# uStar.net
KiCad netlist of a schematic drawn in EAGLE
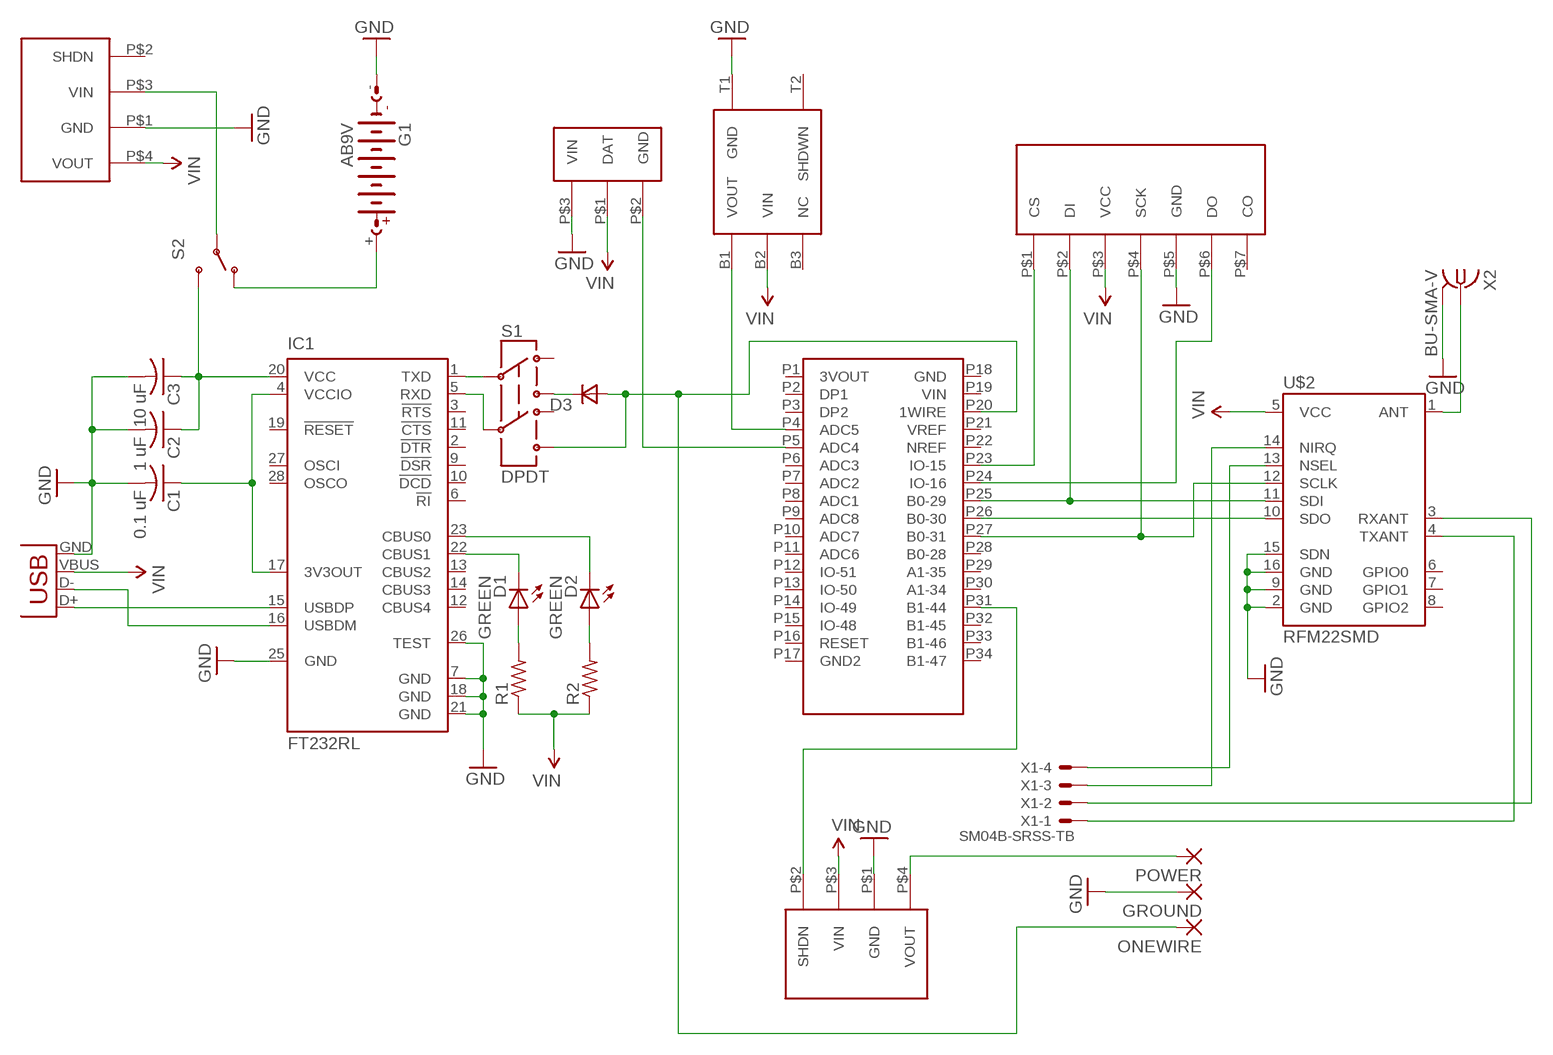
[diagram p0: schematic, sheet 1]

(export (version "E")
  (design (tool "Eeschema 10.0.6"))
  (components
    (comp (ref "C1")
      (value "0.1 uF")
      (footprint "eagle-import:C0805")
      (libsource (lib "eagle-import") (part "C-USC0805"))
    )
    (comp (ref "C2")
      (value "1 uF")
      (footprint "eagle-import:C0805")
      (libsource (lib "eagle-import") (part "C-USC0805"))
    )
    (comp (ref "C3")
      (value "10 uF")
      (footprint "eagle-import:C0805")
      (libsource (lib "eagle-import") (part "C-USC0805"))
    )
    (comp (ref "D1")
      (value "GREEN")
      (footprint "eagle-import:LED-0603")
      (libsource (lib "eagle-import") (part "LED-GREEN0603"))
    )
    (comp (ref "D2")
      (value "GREEN")
      (footprint "eagle-import:LED-0603")
      (libsource (lib "eagle-import") (part "LED-GREEN0603"))
    )
    (comp (ref "D3")
      (value "DSOD323")
      (footprint "eagle-import:SOD323")
      (fields (field (name "MPN") "CDSOD323-T05C"))
      (libsource (lib "eagle-import") (part "DSOD323"))
    )
    (comp (ref "G1")
      (value "AB9V")
      (footprint "eagle-import:AB9V")
      (libsource (lib "eagle-import") (part "AB9V"))
    )
    (comp (ref "GROUND")
      (value "1,6/0,9")
      (footprint "eagle-import:1,6_0,9")
      (libsource (lib "eagle-import") (part "1,6/0,9"))
    )
    (comp (ref "IC1")
      (value "FT232RL")
      (footprint "eagle-import:SSOP28")
      (libsource (lib "eagle-import") (part "FT232RL"))
    )
    (comp (ref "JP1")
      (value "USBSMD")
      (footprint "eagle-import:USB-MINIB")
      (libsource (lib "eagle-import") (part "USBSMD"))
    )
    (comp (ref "ONEWIRE")
      (value "1,6/0,9")
      (footprint "eagle-import:1,6_0,9")
      (libsource (lib "eagle-import") (part "1,6/0,9"))
    )
    (comp (ref "POWER")
      (value "1,6/0,9")
      (footprint "eagle-import:1,6_0,9")
      (libsource (lib "eagle-import") (part "1,6/0,9"))
    )
    (comp (ref "R1")
      (value "R-US_R0603")
      (footprint "eagle-import:R0603")
      (libsource (lib "eagle-import") (part "R-US_R0603"))
    )
    (comp (ref "R2")
      (value "R-US_R0603")
      (footprint "eagle-import:R0603")
      (libsource (lib "eagle-import") (part "R-US_R0603"))
    )
    (comp (ref "S1")
      (value "DPDT")
      (footprint "eagle-import:AYZ0202")
      (libsource (lib "eagle-import") (part "SWITCH-DPDTAYZ0202"))
    )
    (comp (ref "S2")
      (value "SWITCH-SPDTSMD2")
      (footprint "eagle-import:SWITCH-SPDT-SMD")
      (libsource (lib "eagle-import") (part "SWITCH-SPDTSMD2"))
    )
    (comp (ref "U$1")
      (value "APP_CORE")
      (footprint "eagle-import:APPCORE_RECEIVER")
      (libsource (lib "eagle-import") (part "APP_CORE"))
    )
    (comp (ref "U$2")
      (value "RFM22SMD")
      (footprint "eagle-import:RFM22-XXX-S2")
      (libsource (lib "eagle-import") (part "RFM22SMD"))
    )
    (comp (ref "U$3")
      (value "TMP36")
      (footprint "eagle-import:SOT-23-5")
      (libsource (lib "eagle-import") (part "TMP36"))
    )
    (comp (ref "U$4")
      (value "TMP_EXT")
      (footprint "eagle-import:TMP_EXT")
      (libsource (lib "eagle-import") (part "TMP_EXT"))
    )
    (comp (ref "U$5")
      (value "SDCARD_EXT")
      (footprint "eagle-import:SDCARD_EXT")
      (libsource (lib "eagle-import") (part "SDCARD_EXT"))
    )
    (comp (ref "U$6")
      (value "57V8F3_EXT")
      (footprint "eagle-import:S7V8F3_EXT")
      (libsource (lib "eagle-import") (part "57V8F3_EXT"))
    )
    (comp (ref "U$7")
      (value "57V8F3_EXT")
      (footprint "eagle-import:S7V8F3_EXT")
      (libsource (lib "eagle-import") (part "57V8F3_EXT"))
    )
    (comp (ref "X1")
      (value "SM04B-SRSS-TB")
      (footprint "eagle-import:SM04B-SRSS-TB")
      (libsource (lib "eagle-import") (part "?M04B-SRSS-TBS"))
    )
    (comp (ref "X2")
      (value "BU-SMA-V")
      (footprint "eagle-import:BU-SMA-V")
      (libsource (lib "eagle-import") (part "BU-SMA-V"))
    )
  )
  (nets
    (net (code "1") (name "GND") (class "Default")
      (node (ref "C1") (pin "2") (pinfunction "2_2") (pintype "passive"))
      (node (ref "C2") (pin "2") (pinfunction "2_2") (pintype "passive"))
      (node (ref "C3") (pin "2") (pinfunction "2_2") (pintype "passive"))
      (node (ref "G1") (pin "-") (pinfunction "-_-") (pintype "passive"))
      (node (ref "GROUND") (pin "1") (pinfunction "P_1") (pintype "passive"))
      (node (ref "IC1") (pin "18") (pinfunction "GND_18") (pintype "power_in"))
      (node (ref "IC1") (pin "21") (pinfunction "GND_21") (pintype "power_in"))
      (node (ref "IC1") (pin "25") (pinfunction "GND_25") (pintype "power_in"))
      (node (ref "IC1") (pin "26") (pinfunction "TEST_26") (pintype "input"))
      (node (ref "IC1") (pin "7") (pinfunction "GND_7") (pintype "power_in"))
      (node (ref "JP1") (pin "GND") (pinfunction "GND_GND") (pintype "bidirectional"))
      (node (ref "U$2") (pin "15") (pinfunction "SDN_15") (pintype "input"))
      (node (ref "U$2") (pin "16") (pinfunction "GND_16") (pintype "power_in"))
      (node (ref "U$2") (pin "2") (pinfunction "GND_2") (pintype "power_in"))
      (node (ref "U$2") (pin "9") (pinfunction "GND_9") (pintype "power_in"))
      (node (ref "U$3") (pin "T1") (pinfunction "GND_T1") (pintype "bidirectional"))
      (node (ref "U$4") (pin "P$3") (pinfunction "VIN_P$3") (pintype "bidirectional"))
      (node (ref "U$5") (pin "P$5") (pinfunction "GND_P$5") (pintype "bidirectional"))
      (node (ref "U$6") (pin "P$1") (pinfunction "GND_P$1") (pintype "bidirectional"))
      (node (ref "U$7") (pin "P$1") (pinfunction "GND_P$1") (pintype "bidirectional"))
      (node (ref "X2") (pin "2") (pinfunction "2_2") (pintype "passive"))
      (node (ref "X2") (pin "3") (pinfunction "2_3") (pintype "passive"))
      (node (ref "X2") (pin "4") (pinfunction "2_4") (pintype "passive"))
      (node (ref "X2") (pin "5") (pinfunction "2_5") (pintype "passive"))
    )
    (net (code "2") (name "Net-(D1-PadA)") (class "Default")
      (node (ref "D1") (pin "A") (pinfunction "A_A") (pintype "passive"))
      (node (ref "R1") (pin "2") (pinfunction "2_2") (pintype "passive"))
    )
    (net (code "3") (name "Net-(D2-PadA)") (class "Default")
      (node (ref "D2") (pin "A") (pinfunction "A_A") (pintype "passive"))
      (node (ref "R2") (pin "2") (pinfunction "2_2") (pintype "passive"))
    )
    (net (code "4") (name "Net-(D3-A)") (class "Default")
      (node (ref "D3") (pin "2") (pinfunction "A_2") (pintype "passive"))
      (node (ref "ONEWIRE") (pin "1") (pinfunction "P_1") (pintype "passive"))
      (node (ref "S1") (pin "6") (pinfunction "6_6") (pintype "bidirectional"))
      (node (ref "U$1") (pin "P20") (pinfunction "1WIRE_P20") (pintype "bidirectional"))
    )
    (net (code "5") (name "Net-(D3-C)") (class "Default")
      (node (ref "D3") (pin "1") (pinfunction "C_1") (pintype "passive"))
      (node (ref "S1") (pin "3") (pinfunction "3_3") (pintype "bidirectional"))
    )
    (net (code "6") (name "Net-(IC1-3V3OUT)") (class "Default")
      (node (ref "C1") (pin "1") (pinfunction "1_1") (pintype "passive"))
      (node (ref "IC1") (pin "17") (pinfunction "3V3OUT_17") (pintype "output"))
      (node (ref "IC1") (pin "4") (pinfunction "VCCIO_4") (pintype "power_in"))
    )
    (net (code "7") (name "Net-(IC1-CBUS0)") (class "Default")
      (node (ref "D2") (pin "C") (pinfunction "C_C") (pintype "passive"))
      (node (ref "IC1") (pin "23") (pinfunction "CBUS0_23") (pintype "bidirectional"))
    )
    (net (code "8") (name "Net-(IC1-CBUS1)") (class "Default")
      (node (ref "D1") (pin "C") (pinfunction "C_C") (pintype "passive"))
      (node (ref "IC1") (pin "22") (pinfunction "CBUS1_22") (pintype "bidirectional"))
    )
    (net (code "9") (name "Net-(IC1-RXD)") (class "Default")
      (node (ref "IC1") (pin "5") (pinfunction "RXD_5") (pintype "input"))
      (node (ref "S1") (pin "5") (pinfunction "5_5") (pintype "bidirectional"))
    )
    (net (code "10") (name "Net-(IC1-TXD)") (class "Default")
      (node (ref "IC1") (pin "1") (pinfunction "TXD_1") (pintype "output"))
      (node (ref "S1") (pin "2") (pinfunction "2_2") (pintype "bidirectional"))
    )
    (net (code "11") (name "Net-(IC1-USBDM)") (class "Default")
      (node (ref "IC1") (pin "16") (pinfunction "USBDM_16") (pintype "bidirectional"))
      (node (ref "JP1") (pin "D-") (pinfunction "D-_D-") (pintype "bidirectional"))
    )
    (net (code "12") (name "Net-(IC1-USBDP)") (class "Default")
      (node (ref "IC1") (pin "15") (pinfunction "USBDP_15") (pintype "bidirectional"))
      (node (ref "JP1") (pin "D+") (pinfunction "D+_D+") (pintype "bidirectional"))
    )
    (net (code "13") (name "Net-(IC1-VCC)") (class "Default")
      (node (ref "C2") (pin "1") (pinfunction "1_1") (pintype "passive"))
      (node (ref "C3") (pin "1") (pinfunction "1_1") (pintype "passive"))
      (node (ref "IC1") (pin "20") (pinfunction "VCC_20") (pintype "power_in"))
      (node (ref "S2") (pin "3") (pinfunction "S_3") (pintype "passive"))
    )
    (net (code "14") (name "Net-(POWER-P)") (class "Default")
      (node (ref "POWER") (pin "1") (pinfunction "P_1") (pintype "passive"))
      (node (ref "U$7") (pin "P$4") (pinfunction "VOUT_P$4") (pintype "bidirectional"))
    )
    (net (code "15") (name "Net-(S2-O)") (class "Default")
      (node (ref "G1") (pin "+") (pinfunction "+_+") (pintype "passive"))
      (node (ref "S2") (pin "1") (pinfunction "O_1") (pintype "passive"))
    )
    (net (code "16") (name "Net-(S2-P)") (class "Default")
      (node (ref "S2") (pin "2") (pinfunction "P_2") (pintype "passive"))
      (node (ref "U$6") (pin "P$3") (pinfunction "VIN_P$3") (pintype "bidirectional"))
    )
    (net (code "17") (name "Net-(U$1-ADC4)") (class "Default")
      (node (ref "U$1") (pin "P5") (pinfunction "ADC4_P5") (pintype "bidirectional"))
      (node (ref "U$4") (pin "P$2") (pinfunction "GND_P$2") (pintype "bidirectional"))
    )
    (net (code "18") (name "Net-(U$1-ADC5)") (class "Default")
      (node (ref "U$1") (pin "P4") (pinfunction "ADC5_P4") (pintype "bidirectional"))
      (node (ref "U$3") (pin "B1") (pinfunction "VOUT_B1") (pintype "bidirectional"))
    )
    (net (code "19") (name "Net-(U$1-B0-29)") (class "Default")
      (node (ref "U$1") (pin "P25") (pinfunction "B0-29_P25") (pintype "bidirectional"))
      (node (ref "U$2") (pin "11") (pinfunction "SDI_11") (pintype "input"))
      (node (ref "U$5") (pin "P$2") (pinfunction "DI_P$2") (pintype "bidirectional"))
    )
    (net (code "20") (name "Net-(U$1-B0-30)") (class "Default")
      (node (ref "U$1") (pin "P26") (pinfunction "B0-30_P26") (pintype "bidirectional"))
      (node (ref "U$2") (pin "10") (pinfunction "SDO_10") (pintype "output"))
    )
    (net (code "21") (name "Net-(U$1-B0-31)") (class "Default")
      (node (ref "U$1") (pin "P27") (pinfunction "B0-31_P27") (pintype "bidirectional"))
      (node (ref "U$2") (pin "12") (pinfunction "SCLK_12") (pintype "input"))
      (node (ref "U$5") (pin "P$4") (pinfunction "SCK_P$4") (pintype "bidirectional"))
    )
    (net (code "22") (name "Net-(U$1-B1-44)") (class "Default")
      (node (ref "U$1") (pin "P31") (pinfunction "B1-44_P31") (pintype "bidirectional"))
      (node (ref "U$7") (pin "P$2") (pinfunction "SHDN_P$2") (pintype "bidirectional"))
    )
    (net (code "23") (name "Net-(U$1-IO-15)") (class "Default")
      (node (ref "U$1") (pin "P23") (pinfunction "IO-15_P23") (pintype "bidirectional"))
      (node (ref "U$5") (pin "P$1") (pinfunction "CS_P$1") (pintype "bidirectional"))
    )
    (net (code "24") (name "Net-(U$1-IO-16)") (class "Default")
      (node (ref "U$1") (pin "P24") (pinfunction "IO-16_P24") (pintype "bidirectional"))
      (node (ref "U$5") (pin "P$6") (pinfunction "DO_P$6") (pintype "bidirectional"))
    )
    (net (code "25") (name "Net-(U$2-ANT)") (class "Default")
      (node (ref "U$2") (pin "1") (pinfunction "ANT_1") (pintype "bidirectional"))
      (node (ref "X2") (pin "1") (pinfunction "1_1") (pintype "passive"))
    )
    (net (code "26") (name "Net-(U$2-NIRQ)") (class "Default")
      (node (ref "U$2") (pin "14") (pinfunction "NIRQ_14") (pintype "output"))
      (node (ref "X1") (pin "3") (pinfunction "S_3") (pintype "passive"))
    )
    (net (code "27") (name "Net-(U$2-NSEL)") (class "Default")
      (node (ref "U$2") (pin "13") (pinfunction "NSEL_13") (pintype "input"))
      (node (ref "X1") (pin "4") (pinfunction "S_4") (pintype "passive"))
    )
    (net (code "28") (name "Net-(U$2-RXANT)") (class "Default")
      (node (ref "U$2") (pin "3") (pinfunction "RXANT_3") (pintype "input"))
      (node (ref "X1") (pin "2") (pinfunction "S_2") (pintype "passive"))
    )
    (net (code "29") (name "Net-(U$2-TXANT)") (class "Default")
      (node (ref "U$2") (pin "4") (pinfunction "TXANT_4") (pintype "input"))
      (node (ref "X1") (pin "1") (pinfunction "S_1") (pintype "passive"))
    )
    (net (code "30") (name "VIN") (class "Default")
      (node (ref "JP1") (pin "VBUS") (pinfunction "VBUS_VBUS") (pintype "bidirectional"))
      (node (ref "R1") (pin "1") (pinfunction "1_1") (pintype "passive"))
      (node (ref "R2") (pin "1") (pinfunction "1_1") (pintype "passive"))
      (node (ref "U$2") (pin "5") (pinfunction "VCC_5") (pintype "bidirectional"))
      (node (ref "U$3") (pin "B2") (pinfunction "VIN_B2") (pintype "bidirectional"))
      (node (ref "U$4") (pin "P$1") (pinfunction "DAT_P$1") (pintype "bidirectional"))
      (node (ref "U$5") (pin "P$3") (pinfunction "VCC_P$3") (pintype "bidirectional"))
      (node (ref "U$6") (pin "P$4") (pinfunction "VOUT_P$4") (pintype "bidirectional"))
      (node (ref "U$7") (pin "P$3") (pinfunction "VIN_P$3") (pintype "bidirectional"))
    )
    (net (code "31") (name "unconnected-(IC1-CBUS2-Pad13)") (class "Default")
      (node (ref "IC1") (pin "13") (pinfunction "CBUS2_13") (pintype "bidirectional"))
    )
    (net (code "32") (name "unconnected-(IC1-CBUS3-Pad14)") (class "Default")
      (node (ref "IC1") (pin "14") (pinfunction "CBUS3_14") (pintype "bidirectional"))
    )
    (net (code "33") (name "unconnected-(IC1-CBUS4-Pad12)") (class "Default")
      (node (ref "IC1") (pin "12") (pinfunction "CBUS4_12") (pintype "bidirectional"))
    )
    (net (code "34") (name "unconnected-(IC1-OSCI-Pad27)") (class "Default")
      (node (ref "IC1") (pin "27") (pinfunction "OSCI_27") (pintype "input"))
    )
    (net (code "35") (name "unconnected-(IC1-OSCO-Pad28)") (class "Default")
      (node (ref "IC1") (pin "28") (pinfunction "OSCO_28") (pintype "output"))
    )
    (net (code "36") (name "unconnected-(IC1-~{CTS}-Pad11)") (class "Default")
      (node (ref "IC1") (pin "11") (pinfunction "~{CTS}_11") (pintype "input"))
    )
    (net (code "37") (name "unconnected-(IC1-~{DCD}-Pad10)") (class "Default")
      (node (ref "IC1") (pin "10") (pinfunction "~{DCD}_10") (pintype "input"))
    )
    (net (code "38") (name "unconnected-(IC1-~{DSR}-Pad9)") (class "Default")
      (node (ref "IC1") (pin "9") (pinfunction "~{DSR}_9") (pintype "input"))
    )
    (net (code "39") (name "unconnected-(IC1-~{DTR}-Pad2)") (class "Default")
      (node (ref "IC1") (pin "2") (pinfunction "~{DTR}_2") (pintype "output"))
    )
    (net (code "40") (name "unconnected-(IC1-~{RESET}-Pad19)") (class "Default")
      (node (ref "IC1") (pin "19") (pinfunction "~{RESET}_19") (pintype "input"))
    )
    (net (code "41") (name "unconnected-(IC1-~{RI}-Pad6)") (class "Default")
      (node (ref "IC1") (pin "6") (pinfunction "~{RI}_6") (pintype "input"))
    )
    (net (code "42") (name "unconnected-(IC1-~{RTS}-Pad3)") (class "Default")
      (node (ref "IC1") (pin "3") (pinfunction "~{RTS}_3") (pintype "output"))
    )
    (net (code "43") (name "unconnected-(S1-Pad1)") (class "Default")
      (node (ref "S1") (pin "1") (pinfunction "1_1") (pintype "bidirectional"))
    )
    (net (code "44") (name "unconnected-(S1-Pad4)") (class "Default")
      (node (ref "S1") (pin "4") (pinfunction "4_4") (pintype "bidirectional"))
    )
    (net (code "45") (name "unconnected-(U$1-3VOUT-PadP1)") (class "Default")
      (node (ref "U$1") (pin "P1") (pinfunction "3VOUT_P1") (pintype "bidirectional"))
    )
    (net (code "46") (name "unconnected-(U$1-A1-34-PadP30)") (class "Default")
      (node (ref "U$1") (pin "P30") (pinfunction "A1-34_P30") (pintype "bidirectional"))
    )
    (net (code "47") (name "unconnected-(U$1-A1-35-PadP29)") (class "Default")
      (node (ref "U$1") (pin "P29") (pinfunction "A1-35_P29") (pintype "bidirectional"))
    )
    (net (code "48") (name "unconnected-(U$1-ADC1-PadP8)") (class "Default")
      (node (ref "U$1") (pin "P8") (pinfunction "ADC1_P8") (pintype "bidirectional"))
    )
    (net (code "49") (name "unconnected-(U$1-ADC2-PadP7)") (class "Default")
      (node (ref "U$1") (pin "P7") (pinfunction "ADC2_P7") (pintype "bidirectional"))
    )
    (net (code "50") (name "unconnected-(U$1-ADC3-PadP6)") (class "Default")
      (node (ref "U$1") (pin "P6") (pinfunction "ADC3_P6") (pintype "bidirectional"))
    )
    (net (code "51") (name "unconnected-(U$1-ADC6-PadP11)") (class "Default")
      (node (ref "U$1") (pin "P11") (pinfunction "ADC6_P11") (pintype "bidirectional"))
    )
    (net (code "52") (name "unconnected-(U$1-ADC7-PadP10)") (class "Default")
      (node (ref "U$1") (pin "P10") (pinfunction "ADC7_P10") (pintype "bidirectional"))
    )
    (net (code "53") (name "unconnected-(U$1-ADC8-PadP9)") (class "Default")
      (node (ref "U$1") (pin "P9") (pinfunction "ADC8_P9") (pintype "bidirectional"))
    )
    (net (code "54") (name "unconnected-(U$1-B0-28-PadP28)") (class "Default")
      (node (ref "U$1") (pin "P28") (pinfunction "B0-28_P28") (pintype "bidirectional"))
    )
    (net (code "55") (name "unconnected-(U$1-B1-45-PadP32)") (class "Default")
      (node (ref "U$1") (pin "P32") (pinfunction "B1-45_P32") (pintype "bidirectional"))
    )
    (net (code "56") (name "unconnected-(U$1-B1-46-PadP33)") (class "Default")
      (node (ref "U$1") (pin "P33") (pinfunction "B1-46_P33") (pintype "bidirectional"))
    )
    (net (code "57") (name "unconnected-(U$1-B1-47-PadP34)") (class "Default")
      (node (ref "U$1") (pin "P34") (pinfunction "B1-47_P34") (pintype "bidirectional"))
    )
    (net (code "58") (name "unconnected-(U$1-DP1-PadP2)") (class "Default")
      (node (ref "U$1") (pin "P2") (pinfunction "DP1_P2") (pintype "bidirectional"))
    )
    (net (code "59") (name "unconnected-(U$1-DP2-PadP3)") (class "Default")
      (node (ref "U$1") (pin "P3") (pinfunction "DP2_P3") (pintype "bidirectional"))
    )
    (net (code "60") (name "unconnected-(U$1-GND-PadP18)") (class "Default")
      (node (ref "U$1") (pin "P18") (pinfunction "GND_P18") (pintype "bidirectional"))
    )
    (net (code "61") (name "unconnected-(U$1-GND2-PadP17)") (class "Default")
      (node (ref "U$1") (pin "P17") (pinfunction "GND2_P17") (pintype "bidirectional"))
    )
    (net (code "62") (name "unconnected-(U$1-IO-48-PadP15)") (class "Default")
      (node (ref "U$1") (pin "P15") (pinfunction "IO-48_P15") (pintype "bidirectional"))
    )
    (net (code "63") (name "unconnected-(U$1-IO-49-PadP14)") (class "Default")
      (node (ref "U$1") (pin "P14") (pinfunction "IO-49_P14") (pintype "bidirectional"))
    )
    (net (code "64") (name "unconnected-(U$1-IO-50-PadP13)") (class "Default")
      (node (ref "U$1") (pin "P13") (pinfunction "IO-50_P13") (pintype "bidirectional"))
    )
    (net (code "65") (name "unconnected-(U$1-IO-51-PadP12)") (class "Default")
      (node (ref "U$1") (pin "P12") (pinfunction "IO-51_P12") (pintype "bidirectional"))
    )
    (net (code "66") (name "unconnected-(U$1-NREF-PadP22)") (class "Default")
      (node (ref "U$1") (pin "P22") (pinfunction "NREF_P22") (pintype "bidirectional"))
    )
    (net (code "67") (name "unconnected-(U$1-RESET-PadP16)") (class "Default")
      (node (ref "U$1") (pin "P16") (pinfunction "RESET_P16") (pintype "bidirectional"))
    )
    (net (code "68") (name "unconnected-(U$1-VIN-PadP19)") (class "Default")
      (node (ref "U$1") (pin "P19") (pinfunction "VIN_P19") (pintype "bidirectional"))
    )
    (net (code "69") (name "unconnected-(U$1-VREF-PadP21)") (class "Default")
      (node (ref "U$1") (pin "P21") (pinfunction "VREF_P21") (pintype "bidirectional"))
    )
    (net (code "70") (name "unconnected-(U$2-GPIO0-Pad6)") (class "Default")
      (node (ref "U$2") (pin "6") (pinfunction "GPIO0_6") (pintype "bidirectional"))
    )
    (net (code "71") (name "unconnected-(U$2-GPIO1-Pad7)") (class "Default")
      (node (ref "U$2") (pin "7") (pinfunction "GPIO1_7") (pintype "bidirectional"))
    )
    (net (code "72") (name "unconnected-(U$2-GPIO2-Pad8)") (class "Default")
      (node (ref "U$2") (pin "8") (pinfunction "GPIO2_8") (pintype "bidirectional"))
    )
    (net (code "73") (name "unconnected-(U$3-NC-PadB3)") (class "Default")
      (node (ref "U$3") (pin "B3") (pinfunction "NC_B3") (pintype "bidirectional"))
    )
    (net (code "74") (name "unconnected-(U$3-SHDWN-PadT2)") (class "Default")
      (node (ref "U$3") (pin "T2") (pinfunction "SHDWN_T2") (pintype "bidirectional"))
    )
    (net (code "75") (name "unconnected-(U$5-CO-PadP$7)") (class "Default")
      (node (ref "U$5") (pin "P$7") (pinfunction "CO_P$7") (pintype "bidirectional"))
    )
    (net (code "76") (name "unconnected-(U$6-SHDN-PadP$2)") (class "Default")
      (node (ref "U$6") (pin "P$2") (pinfunction "SHDN_P$2") (pintype "bidirectional"))
    )
  )
)
